# ESP8266_Single_RGB_RevC.net
KiCad netlist of a schematic drawn in EAGLE
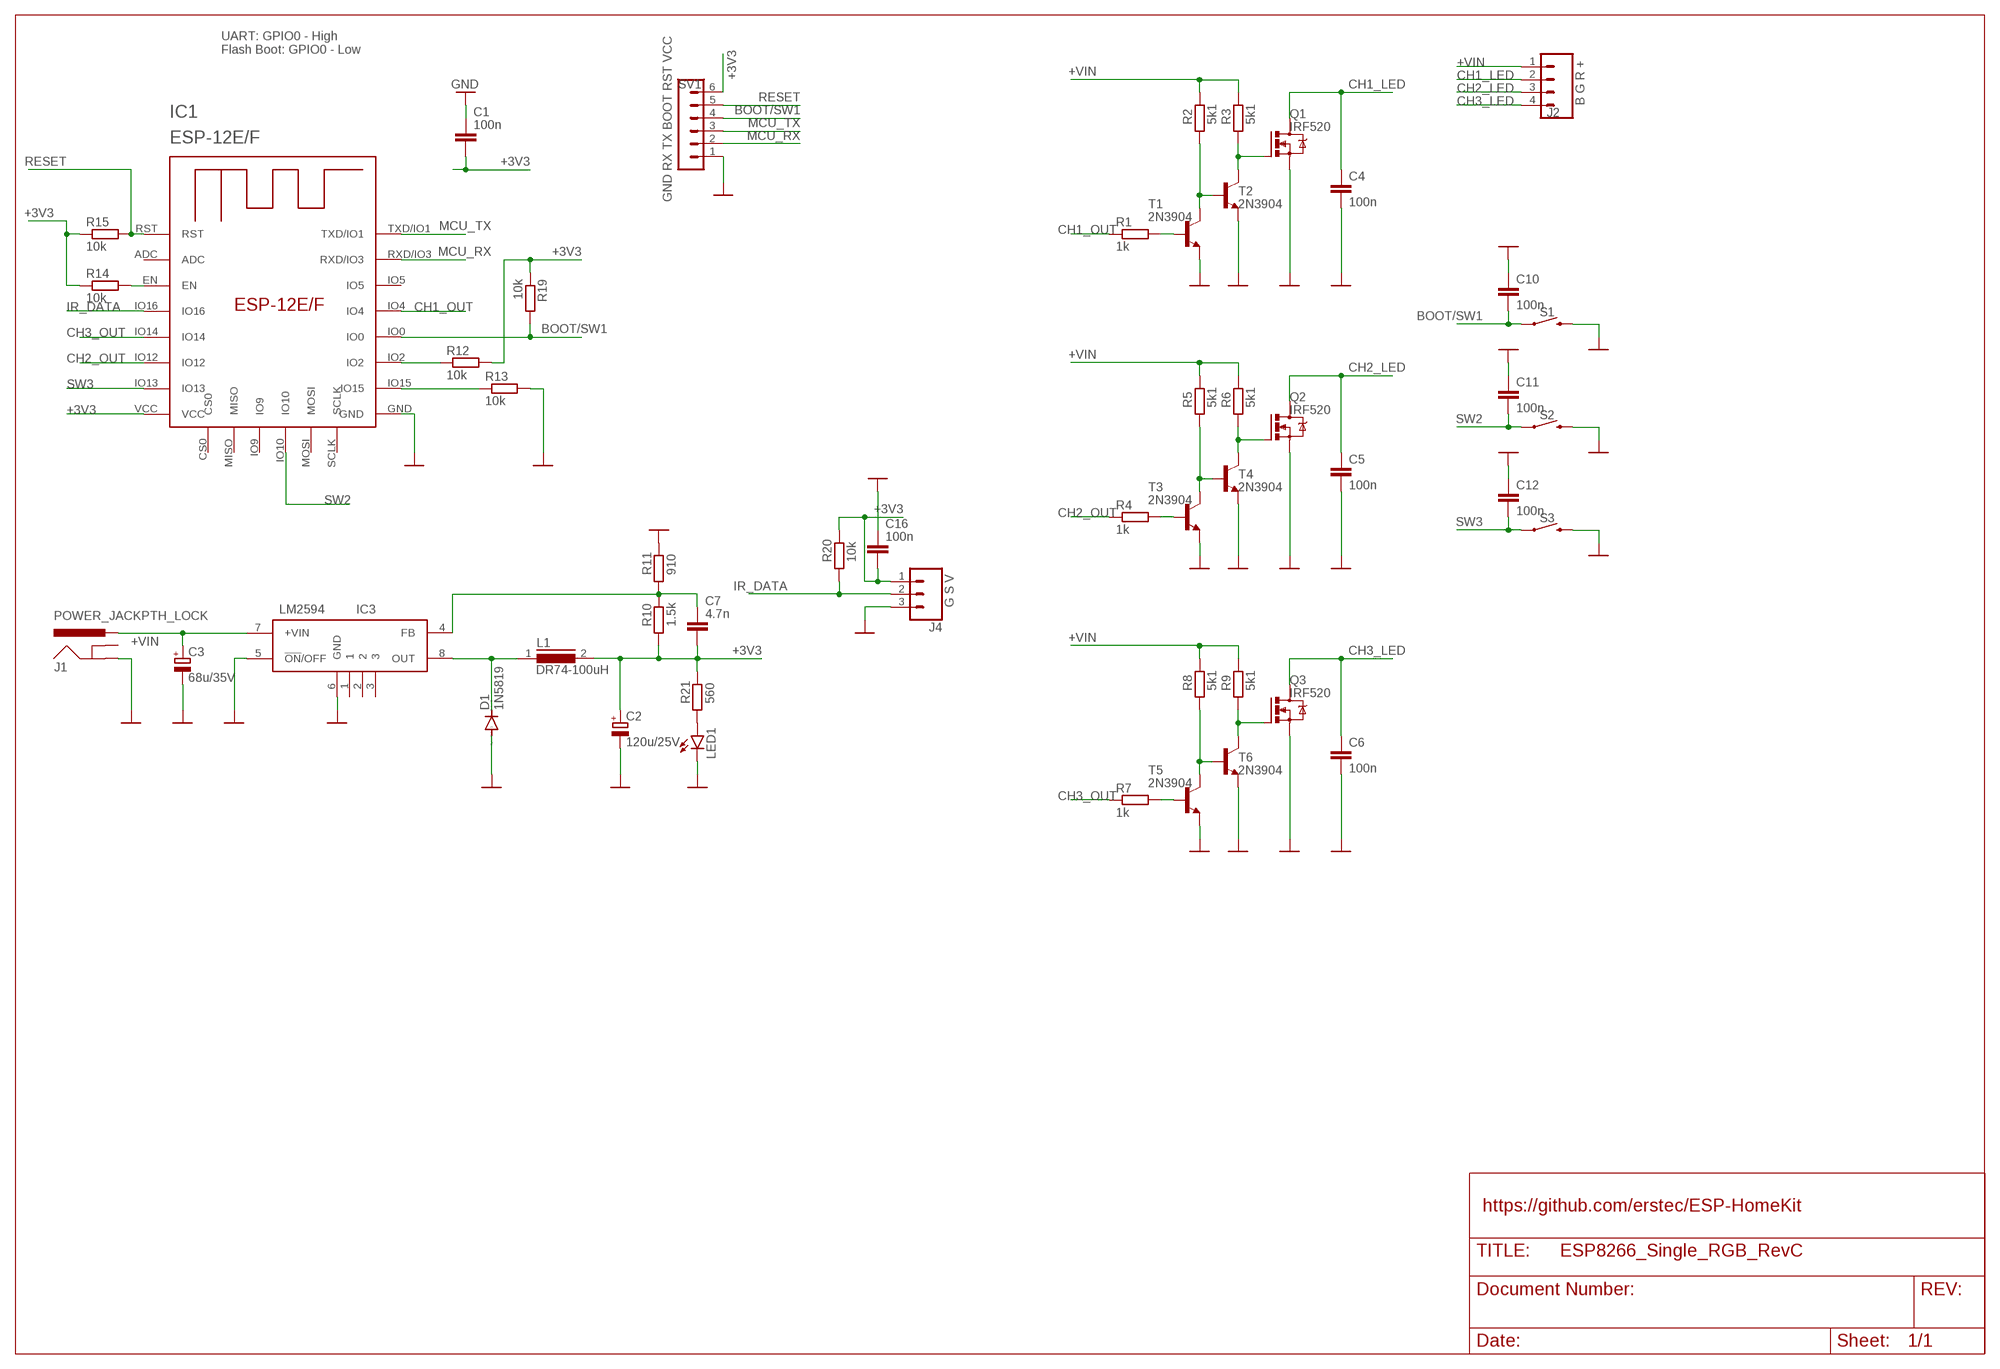
[diagram p0: schematic, sheet 1]

(export (version "E")
  (design (tool "Eeschema 10.0.6"))
  (components
    (comp (ref "C1")
      (value "100n")
      (footprint "eagle-import:C050-024X044")
      (libsource (lib "eagle-import") (part "C-EU050-024X044"))
    )
    (comp (ref "C2")
      (value "120u/25V")
      (footprint "eagle-import:E2,5-6E")
      (libsource (lib "eagle-import") (part "CPOL-EUE2,5-6E"))
    )
    (comp (ref "C3")
      (value "68u/35V")
      (footprint "eagle-import:E2,5-6")
      (libsource (lib "eagle-import") (part "CPOL-EUE2.5-6"))
    )
    (comp (ref "C4")
      (value "100n")
      (footprint "eagle-import:C050-024X044")
      (libsource (lib "eagle-import") (part "C-EU050-024X044"))
    )
    (comp (ref "C5")
      (value "100n")
      (footprint "eagle-import:C050-024X044")
      (libsource (lib "eagle-import") (part "C-EU050-024X044"))
    )
    (comp (ref "C6")
      (value "100n")
      (footprint "eagle-import:C050-024X044")
      (libsource (lib "eagle-import") (part "C-EU050-024X044"))
    )
    (comp (ref "C7")
      (value "4.7n")
      (footprint "eagle-import:C0805")
      (libsource (lib "eagle-import") (part "C-EUC0805"))
    )
    (comp (ref "C10")
      (value "100n")
      (footprint "eagle-import:C050-024X044")
      (libsource (lib "eagle-import") (part "C-EU050-024X044"))
    )
    (comp (ref "C11")
      (value "100n")
      (footprint "eagle-import:C050-024X044")
      (libsource (lib "eagle-import") (part "C-EU050-024X044"))
    )
    (comp (ref "C12")
      (value "100n")
      (footprint "eagle-import:C050-024X044")
      (libsource (lib "eagle-import") (part "C-EU050-024X044"))
    )
    (comp (ref "C16")
      (value "100n")
      (footprint "eagle-import:C050-024X044")
      (libsource (lib "eagle-import") (part "C-EU050-024X044"))
    )
    (comp (ref "D1")
      (value "1N5819")
      (footprint "eagle-import:DO41-7.6")
      (libsource (lib "eagle-import") (part "DIODE-DO41-7.6"))
    )
    (comp (ref "IC1")
      (value "ESP-12E/F")
      (footprint "eagle-import:ESP-12E")
      (libsource (lib "eagle-import") (part "ESP-12E/F"))
    )
    (comp (ref "IC3")
      (value "LM2594")
      (footprint "eagle-import:TSOP8")
      (fields (field (name "MF") "National Semiconductor"))
      (libsource (lib "eagle-import") (part "LM2594"))
    )
    (comp (ref "J1")
      (value "POWER_JACKPTH_LOCK")
      (footprint "eagle-import:POWER_JACK_PTH_LOCK")
      (libsource (lib "eagle-import") (part "POWER_JACKPTH_LOCK"))
    )
    (comp (ref "J2")
      (value "B G R +")
      (footprint "eagle-import:SCREWTERMINAL-3.5MM-4_LOCK")
      (libsource (lib "eagle-import") (part "CONN_04SCREW_LOCK"))
    )
    (comp (ref "J4")
      (value "G S V")
      (footprint "eagle-import:SCREWTERMINAL-3.5MM-3_LOCK.007S")
      (libsource (lib "eagle-import") (part "CONN_03SCREW_LOCK"))
    )
    (comp (ref "L1")
      (value "DR74-100uH")
      (footprint "eagle-import:DR74")
      (libsource (lib "eagle-import") (part "DR74"))
    )
    (comp (ref "LED1")
      (value "LED5MM")
      (footprint "eagle-import:LED5MM")
      (libsource (lib "eagle-import") (part "LED5MM"))
    )
    (comp (ref "Q1")
      (value "IRF520")
      (footprint "eagle-import:TO220BV")
      (libsource (lib "eagle-import") (part "IRF520"))
    )
    (comp (ref "Q2")
      (value "IRF520")
      (footprint "eagle-import:TO220BV")
      (libsource (lib "eagle-import") (part "IRF520"))
    )
    (comp (ref "Q3")
      (value "IRF520")
      (footprint "eagle-import:TO220BV")
      (libsource (lib "eagle-import") (part "IRF520"))
    )
    (comp (ref "R1")
      (value "1k")
      (footprint "eagle-import:0204_7")
      (libsource (lib "eagle-import") (part "R-EU_0204/7"))
    )
    (comp (ref "R2")
      (value "5k1")
      (footprint "eagle-import:0204_7")
      (libsource (lib "eagle-import") (part "R-EU_0204/7"))
    )
    (comp (ref "R3")
      (value "5k1")
      (footprint "eagle-import:0204_7")
      (libsource (lib "eagle-import") (part "R-EU_0204/7"))
    )
    (comp (ref "R4")
      (value "1k")
      (footprint "eagle-import:0204_7")
      (libsource (lib "eagle-import") (part "R-EU_0204/7"))
    )
    (comp (ref "R5")
      (value "5k1")
      (footprint "eagle-import:0204_7")
      (libsource (lib "eagle-import") (part "R-EU_0204/7"))
    )
    (comp (ref "R6")
      (value "5k1")
      (footprint "eagle-import:0204_7")
      (libsource (lib "eagle-import") (part "R-EU_0204/7"))
    )
    (comp (ref "R7")
      (value "1k")
      (footprint "eagle-import:0204_7")
      (libsource (lib "eagle-import") (part "R-EU_0204/7"))
    )
    (comp (ref "R8")
      (value "5k1")
      (footprint "eagle-import:0204_7")
      (libsource (lib "eagle-import") (part "R-EU_0204/7"))
    )
    (comp (ref "R9")
      (value "5k1")
      (footprint "eagle-import:0204_7")
      (libsource (lib "eagle-import") (part "R-EU_0204/7"))
    )
    (comp (ref "R10")
      (value "1.5k")
      (footprint "eagle-import:M0805")
      (libsource (lib "eagle-import") (part "R-EU_M0805"))
    )
    (comp (ref "R11")
      (value "910")
      (footprint "eagle-import:R0805")
      (libsource (lib "eagle-import") (part "R-EU_R0805"))
    )
    (comp (ref "R12")
      (value "10k")
      (footprint "eagle-import:0204_7")
      (libsource (lib "eagle-import") (part "R-EU_0204/7"))
    )
    (comp (ref "R13")
      (value "10k")
      (footprint "eagle-import:0204_7")
      (libsource (lib "eagle-import") (part "R-EU_0204/7"))
    )
    (comp (ref "R14")
      (value "10k")
      (footprint "eagle-import:0204_7")
      (libsource (lib "eagle-import") (part "R-EU_0204/7"))
    )
    (comp (ref "R15")
      (value "10k")
      (footprint "eagle-import:0204_7")
      (libsource (lib "eagle-import") (part "R-EU_0204/7"))
    )
    (comp (ref "R19")
      (value "10k")
      (footprint "eagle-import:0204_7")
      (libsource (lib "eagle-import") (part "R-EU_0204/7"))
    )
    (comp (ref "R20")
      (value "10k")
      (footprint "eagle-import:0204_7")
      (libsource (lib "eagle-import") (part "R-EU_0204/7"))
    )
    (comp (ref "R21")
      (value "560")
      (footprint "eagle-import:0204_7")
      (libsource (lib "eagle-import") (part "R-EU_0204/7"))
    )
    (comp (ref "S1")
      (value "MOMENTARY-SWITCH-SPST-PTH-6.0MM")
      (footprint "eagle-import:TACTILE_SWITCH_PTH_6.0MM")
      (libsource (lib "eagle-import") (part "MOMENTARY-SWITCH-SPST-PTH-6.0MM"))
    )
    (comp (ref "S2")
      (value "MOMENTARY-SWITCH-SPST-PTH-6.0MM")
      (footprint "eagle-import:TACTILE_SWITCH_PTH_6.0MM")
      (libsource (lib "eagle-import") (part "MOMENTARY-SWITCH-SPST-PTH-6.0MM"))
    )
    (comp (ref "S3")
      (value "MOMENTARY-SWITCH-SPST-PTH-6.0MM")
      (footprint "eagle-import:TACTILE_SWITCH_PTH_6.0MM")
      (libsource (lib "eagle-import") (part "MOMENTARY-SWITCH-SPST-PTH-6.0MM"))
    )
    (comp (ref "SV1")
      (value "GND RX TX BOOT RST VCC")
      (footprint "eagle-import:MA06-1")
      (libsource (lib "eagle-import") (part "MA06-1"))
    )
    (comp (ref "T1")
      (value "2N3904")
      (footprint "eagle-import:TO92-EBC")
      (libsource (lib "eagle-import") (part "-NPN-TO92-EBC2N3904"))
    )
    (comp (ref "T2")
      (value "2N3904")
      (footprint "eagle-import:TO92-EBC")
      (libsource (lib "eagle-import") (part "-NPN-TO92-EBC2N3904"))
    )
    (comp (ref "T3")
      (value "2N3904")
      (footprint "eagle-import:TO92-EBC")
      (libsource (lib "eagle-import") (part "-NPN-TO92-EBC2N3904"))
    )
    (comp (ref "T4")
      (value "2N3904")
      (footprint "eagle-import:TO92-EBC")
      (libsource (lib "eagle-import") (part "-NPN-TO92-EBC2N3904"))
    )
    (comp (ref "T5")
      (value "2N3904")
      (footprint "eagle-import:TO92-EBC")
      (libsource (lib "eagle-import") (part "-NPN-TO92-EBC2N3904"))
    )
    (comp (ref "T6")
      (value "2N3904")
      (footprint "eagle-import:TO92-EBC")
      (libsource (lib "eagle-import") (part "-NPN-TO92-EBC2N3904"))
    )
  )
  (nets
    (net (code "1") (name "/+3V3") (class "Default")
      (node (ref "C1") (pin "2") (pinfunction "2_2") (pintype "passive"))
      (node (ref "C16") (pin "2") (pinfunction "2_2") (pintype "passive"))
      (node (ref "C2") (pin "+") (pinfunction "+_+") (pintype "passive"))
      (node (ref "C7") (pin "2") (pinfunction "2_2") (pintype "passive"))
      (node (ref "IC1") (pin "VCC") (pinfunction "VCC_VCC") (pintype "power_in"))
      (node (ref "J4") (pin "1") (pinfunction "1_1") (pintype "passive"))
      (node (ref "L1") (pin "2") (pinfunction "2_2") (pintype "passive"))
      (node (ref "R10") (pin "1") (pinfunction "1_1") (pintype "passive"))
      (node (ref "R12") (pin "2") (pinfunction "2_2") (pintype "passive"))
      (node (ref "R14") (pin "1") (pinfunction "1_1") (pintype "passive"))
      (node (ref "R15") (pin "1") (pinfunction "1_1") (pintype "passive"))
      (node (ref "R19") (pin "1") (pinfunction "1_1") (pintype "passive"))
      (node (ref "R20") (pin "2") (pinfunction "2_2") (pintype "passive"))
      (node (ref "R21") (pin "2") (pinfunction "2_2") (pintype "passive"))
      (node (ref "SV1") (pin "6") (pinfunction "6_6") (pintype "passive"))
    )
    (net (code "2") (name "/+VIN") (class "Default")
      (node (ref "C3") (pin "+") (pinfunction "+_+") (pintype "passive"))
      (node (ref "IC3") (pin "7") (pinfunction "+VIN_7") (pintype "bidirectional"))
      (node (ref "J1") (pin "PWR") (pinfunction "PWR_PWR") (pintype "bidirectional"))
      (node (ref "J2") (pin "1") (pinfunction "1_1") (pintype "passive"))
      (node (ref "R2") (pin "2") (pinfunction "2_2") (pintype "passive"))
      (node (ref "R3") (pin "2") (pinfunction "2_2") (pintype "passive"))
      (node (ref "R5") (pin "2") (pinfunction "2_2") (pintype "passive"))
      (node (ref "R6") (pin "2") (pinfunction "2_2") (pintype "passive"))
      (node (ref "R8") (pin "2") (pinfunction "2_2") (pintype "passive"))
      (node (ref "R9") (pin "2") (pinfunction "2_2") (pintype "passive"))
    )
    (net (code "3") (name "/BOOT{slash}SW1") (class "Default")
      (node (ref "C10") (pin "2") (pinfunction "2_2") (pintype "passive"))
      (node (ref "IC1") (pin "IO0") (pinfunction "IO0_IO0") (pintype "bidirectional"))
      (node (ref "R19") (pin "2") (pinfunction "2_2") (pintype "passive"))
      (node (ref "S1") (pin "1") (pinfunction "1_1") (pintype "passive"))
      (node (ref "SV1") (pin "4") (pinfunction "4_4") (pintype "passive"))
    )
    (net (code "4") (name "/CH1_LED") (class "Default")
      (node (ref "C4") (pin "1") (pinfunction "1_1") (pintype "passive"))
      (node (ref "J2") (pin "2") (pinfunction "2_2") (pintype "passive"))
      (node (ref "Q1") (pin "D") (pinfunction "D_D") (pintype "passive"))
    )
    (net (code "5") (name "/CH1_OUT") (class "Default")
      (node (ref "IC1") (pin "IO4") (pinfunction "IO4_IO4") (pintype "bidirectional"))
      (node (ref "R1") (pin "1") (pinfunction "1_1") (pintype "passive"))
    )
    (net (code "6") (name "/CH2_LED") (class "Default")
      (node (ref "C5") (pin "1") (pinfunction "1_1") (pintype "passive"))
      (node (ref "J2") (pin "3") (pinfunction "3_3") (pintype "passive"))
      (node (ref "Q2") (pin "D") (pinfunction "D_D") (pintype "passive"))
    )
    (net (code "7") (name "/CH2_OUT") (class "Default")
      (node (ref "IC1") (pin "IO12") (pinfunction "IO12_IO12") (pintype "bidirectional"))
      (node (ref "R4") (pin "1") (pinfunction "1_1") (pintype "passive"))
    )
    (net (code "8") (name "/CH3_LED") (class "Default")
      (node (ref "C6") (pin "1") (pinfunction "1_1") (pintype "passive"))
      (node (ref "J2") (pin "4") (pinfunction "4_4") (pintype "passive"))
      (node (ref "Q3") (pin "D") (pinfunction "D_D") (pintype "passive"))
    )
    (net (code "9") (name "/CH3_OUT") (class "Default")
      (node (ref "IC1") (pin "IO14") (pinfunction "IO14_IO14") (pintype "bidirectional"))
      (node (ref "R7") (pin "1") (pinfunction "1_1") (pintype "passive"))
    )
    (net (code "10") (name "/IR_DATA") (class "Default")
      (node (ref "IC1") (pin "IO16") (pinfunction "IO16_IO16") (pintype "bidirectional"))
      (node (ref "J4") (pin "2") (pinfunction "2_2") (pintype "passive"))
      (node (ref "R20") (pin "1") (pinfunction "1_1") (pintype "passive"))
    )
    (net (code "11") (name "/MCU_RX") (class "Default")
      (node (ref "IC1") (pin "RXD/IO3") (pinfunction "RXD/IO3_RXD/IO3") (pintype "bidirectional"))
      (node (ref "SV1") (pin "2") (pinfunction "2_2") (pintype "passive"))
    )
    (net (code "12") (name "/MCU_TX") (class "Default")
      (node (ref "IC1") (pin "TXD/IO1") (pinfunction "TXD/IO1_TXD/IO1") (pintype "bidirectional"))
      (node (ref "SV1") (pin "3") (pinfunction "3_3") (pintype "passive"))
    )
    (net (code "13") (name "/RESET") (class "Default")
      (node (ref "IC1") (pin "RST") (pinfunction "RST_RST") (pintype "input"))
      (node (ref "R15") (pin "2") (pinfunction "2_2") (pintype "passive"))
      (node (ref "SV1") (pin "5") (pinfunction "5_5") (pintype "passive"))
    )
    (net (code "14") (name "/SW2") (class "Default")
      (node (ref "C11") (pin "2") (pinfunction "2_2") (pintype "passive"))
      (node (ref "IC1") (pin "IO10") (pinfunction "IO10_IO10") (pintype "bidirectional"))
      (node (ref "S2") (pin "1") (pinfunction "1_1") (pintype "passive"))
    )
    (net (code "15") (name "/SW3") (class "Default")
      (node (ref "C12") (pin "2") (pinfunction "2_2") (pintype "passive"))
      (node (ref "IC1") (pin "IO13") (pinfunction "IO13_IO13") (pintype "bidirectional"))
      (node (ref "S3") (pin "1") (pinfunction "1_1") (pintype "passive"))
    )
    (net (code "16") (name "GND") (class "Default")
      (node (ref "C1") (pin "1") (pinfunction "1_1") (pintype "passive"))
      (node (ref "C10") (pin "1") (pinfunction "1_1") (pintype "passive"))
      (node (ref "C11") (pin "1") (pinfunction "1_1") (pintype "passive"))
      (node (ref "C12") (pin "1") (pinfunction "1_1") (pintype "passive"))
      (node (ref "C16") (pin "1") (pinfunction "1_1") (pintype "passive"))
      (node (ref "C2") (pin "-") (pinfunction "-_-") (pintype "passive"))
      (node (ref "C3") (pin "-") (pinfunction "-_-") (pintype "passive"))
      (node (ref "C4") (pin "2") (pinfunction "2_2") (pintype "passive"))
      (node (ref "C5") (pin "2") (pinfunction "2_2") (pintype "passive"))
      (node (ref "C6") (pin "2") (pinfunction "2_2") (pintype "passive"))
      (node (ref "D1") (pin "A") (pinfunction "A_A") (pintype "passive"))
      (node (ref "IC1") (pin "GND") (pinfunction "GND_GND") (pintype "power_in"))
      (node (ref "IC3") (pin "5") (pinfunction "~{ON}/OFF_5") (pintype "bidirectional"))
      (node (ref "IC3") (pin "6") (pinfunction "GND_6") (pintype "bidirectional"))
      (node (ref "J1") (pin "GND") (pinfunction "GND_GND") (pintype "bidirectional"))
      (node (ref "J4") (pin "3") (pinfunction "3_3") (pintype "passive"))
      (node (ref "LED1") (pin "K") (pinfunction "C_K") (pintype "passive"))
      (node (ref "Q1") (pin "S") (pinfunction "S_S") (pintype "passive"))
      (node (ref "Q2") (pin "S") (pinfunction "S_S") (pintype "passive"))
      (node (ref "Q3") (pin "S") (pinfunction "S_S") (pintype "passive"))
      (node (ref "R11") (pin "2") (pinfunction "2_2") (pintype "passive"))
      (node (ref "R13") (pin "2") (pinfunction "2_2") (pintype "passive"))
      (node (ref "S1") (pin "3") (pinfunction "2_3") (pintype "passive"))
      (node (ref "S2") (pin "3") (pinfunction "2_3") (pintype "passive"))
      (node (ref "S3") (pin "3") (pinfunction "2_3") (pintype "passive"))
      (node (ref "SV1") (pin "1") (pinfunction "1_1") (pintype "passive"))
      (node (ref "T1") (pin "E") (pinfunction "E_E") (pintype "passive"))
      (node (ref "T2") (pin "E") (pinfunction "E_E") (pintype "passive"))
      (node (ref "T3") (pin "E") (pinfunction "E_E") (pintype "passive"))
      (node (ref "T4") (pin "E") (pinfunction "E_E") (pintype "passive"))
      (node (ref "T5") (pin "E") (pinfunction "E_E") (pintype "passive"))
      (node (ref "T6") (pin "E") (pinfunction "E_E") (pintype "passive"))
    )
    (net (code "17") (name "Net-(IC1-PadEN)") (class "Default")
      (node (ref "IC1") (pin "EN") (pinfunction "EN_EN") (pintype "bidirectional"))
      (node (ref "R14") (pin "2") (pinfunction "2_2") (pintype "passive"))
    )
    (net (code "18") (name "Net-(IC1-PadIO2)") (class "Default")
      (node (ref "IC1") (pin "IO2") (pinfunction "IO2_IO2") (pintype "bidirectional"))
      (node (ref "R12") (pin "1") (pinfunction "1_1") (pintype "passive"))
    )
    (net (code "19") (name "Net-(IC1-PadIO15)") (class "Default")
      (node (ref "IC1") (pin "IO15") (pinfunction "IO15_IO15") (pintype "bidirectional"))
      (node (ref "R13") (pin "1") (pinfunction "1_1") (pintype "passive"))
    )
    (net (code "20") (name "Net-(IC3-FB)") (class "Default")
      (node (ref "C7") (pin "1") (pinfunction "1_1") (pintype "passive"))
      (node (ref "IC3") (pin "4") (pinfunction "FB_4") (pintype "bidirectional"))
      (node (ref "R10") (pin "2") (pinfunction "2_2") (pintype "passive"))
      (node (ref "R11") (pin "1") (pinfunction "1_1") (pintype "passive"))
    )
    (net (code "21") (name "Net-(IC3-OUT)") (class "Default")
      (node (ref "D1") (pin "C") (pinfunction "C_C") (pintype "passive"))
      (node (ref "IC3") (pin "8") (pinfunction "OUT_8") (pintype "bidirectional"))
      (node (ref "L1") (pin "1") (pinfunction "1_1") (pintype "passive"))
    )
    (net (code "22") (name "Net-(LED1-PadA)") (class "Default")
      (node (ref "LED1") (pin "A") (pinfunction "A_A") (pintype "passive"))
      (node (ref "R21") (pin "1") (pinfunction "1_1") (pintype "passive"))
    )
    (net (code "23") (name "Net-(Q1-PadG)") (class "Default")
      (node (ref "Q1") (pin "G") (pinfunction "G_G") (pintype "passive"))
      (node (ref "R3") (pin "1") (pinfunction "1_1") (pintype "passive"))
      (node (ref "T2") (pin "C") (pinfunction "C_C") (pintype "passive"))
    )
    (net (code "24") (name "Net-(Q2-PadG)") (class "Default")
      (node (ref "Q2") (pin "G") (pinfunction "G_G") (pintype "passive"))
      (node (ref "R6") (pin "1") (pinfunction "1_1") (pintype "passive"))
      (node (ref "T4") (pin "C") (pinfunction "C_C") (pintype "passive"))
    )
    (net (code "25") (name "Net-(Q3-PadG)") (class "Default")
      (node (ref "Q3") (pin "G") (pinfunction "G_G") (pintype "passive"))
      (node (ref "R9") (pin "1") (pinfunction "1_1") (pintype "passive"))
      (node (ref "T6") (pin "C") (pinfunction "C_C") (pintype "passive"))
    )
    (net (code "26") (name "Net-(R1-Pad2)") (class "Default")
      (node (ref "R1") (pin "2") (pinfunction "2_2") (pintype "passive"))
      (node (ref "T1") (pin "B") (pinfunction "B_B") (pintype "passive"))
    )
    (net (code "27") (name "Net-(R2-Pad1)") (class "Default")
      (node (ref "R2") (pin "1") (pinfunction "1_1") (pintype "passive"))
      (node (ref "T1") (pin "C") (pinfunction "C_C") (pintype "passive"))
      (node (ref "T2") (pin "B") (pinfunction "B_B") (pintype "passive"))
    )
    (net (code "28") (name "Net-(R4-Pad2)") (class "Default")
      (node (ref "R4") (pin "2") (pinfunction "2_2") (pintype "passive"))
      (node (ref "T3") (pin "B") (pinfunction "B_B") (pintype "passive"))
    )
    (net (code "29") (name "Net-(R5-Pad1)") (class "Default")
      (node (ref "R5") (pin "1") (pinfunction "1_1") (pintype "passive"))
      (node (ref "T3") (pin "C") (pinfunction "C_C") (pintype "passive"))
      (node (ref "T4") (pin "B") (pinfunction "B_B") (pintype "passive"))
    )
    (net (code "30") (name "Net-(R7-Pad2)") (class "Default")
      (node (ref "R7") (pin "2") (pinfunction "2_2") (pintype "passive"))
      (node (ref "T5") (pin "B") (pinfunction "B_B") (pintype "passive"))
    )
    (net (code "31") (name "Net-(R8-Pad1)") (class "Default")
      (node (ref "R8") (pin "1") (pinfunction "1_1") (pintype "passive"))
      (node (ref "T5") (pin "C") (pinfunction "C_C") (pintype "passive"))
      (node (ref "T6") (pin "B") (pinfunction "B_B") (pintype "passive"))
    )
    (net (code "32") (name "unconnected-(IC1-PadADC)") (class "Default")
      (node (ref "IC1") (pin "ADC") (pinfunction "ADC_ADC") (pintype "bidirectional"))
    )
    (net (code "33") (name "unconnected-(IC1-PadCS0)") (class "Default")
      (node (ref "IC1") (pin "CS0") (pinfunction "CS0_CS0") (pintype "bidirectional"))
    )
    (net (code "34") (name "unconnected-(IC1-PadIO5)") (class "Default")
      (node (ref "IC1") (pin "IO5") (pinfunction "IO5_IO5") (pintype "bidirectional"))
    )
    (net (code "35") (name "unconnected-(IC1-PadIO9)") (class "Default")
      (node (ref "IC1") (pin "IO9") (pinfunction "IO9_IO9") (pintype "bidirectional"))
    )
    (net (code "36") (name "unconnected-(IC1-PadMISO)") (class "Default")
      (node (ref "IC1") (pin "MISO") (pinfunction "MISO_MISO") (pintype "bidirectional"))
    )
    (net (code "37") (name "unconnected-(IC1-PadMOSI)") (class "Default")
      (node (ref "IC1") (pin "MOSI") (pinfunction "MOSI_MOSI") (pintype "bidirectional"))
    )
    (net (code "38") (name "unconnected-(IC1-PadSCLK)") (class "Default")
      (node (ref "IC1") (pin "SCLK") (pinfunction "SCLK_SCLK") (pintype "bidirectional"))
    )
    (net (code "39") (name "unconnected-(IC3-Pad1)") (class "Default")
      (node (ref "IC3") (pin "1") (pinfunction "1_1") (pintype "bidirectional"))
    )
    (net (code "40") (name "unconnected-(IC3-Pad2)") (class "Default")
      (node (ref "IC3") (pin "2") (pinfunction "2_2") (pintype "bidirectional"))
    )
    (net (code "41") (name "unconnected-(IC3-Pad3)") (class "Default")
      (node (ref "IC3") (pin "3") (pinfunction "3_3") (pintype "bidirectional"))
    )
    (net (code "42") (name "unconnected-(J1-PadGNDBREAK)") (class "Default")
      (node (ref "J1") (pin "GNDBREAK") (pinfunction "GNDBREAK_GNDBREAK") (pintype "bidirectional"))
    )
  )
)
